# LED_Power_Ind.net
KiCad netlist of a schematic drawn in Altium Designer
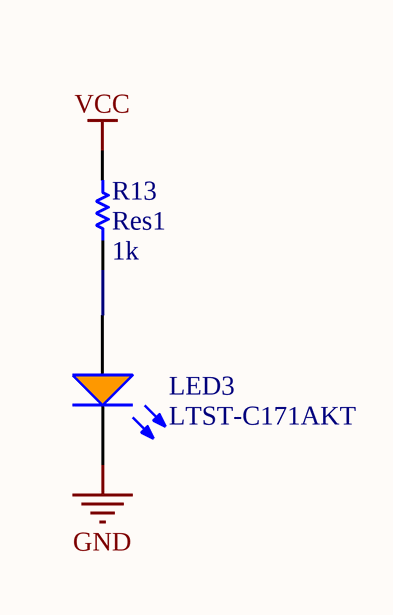
[diagram p0: LED_Power_Ind.SchDoc]

(export (version "E")
  (design (tool "Eeschema 10.0.6"))
  (components
    (comp (ref "LED3")
      (value "LTST-C171AKT")
      (footprint "LTST-C171AKT_V")
      (description "LED Uni-Color Orange, 100 mW, 120 mA, -55 to 85 degC, 2-Pin SMD, RoHS, Tape and Reel")
      (fields (field (name "MANUFACTURER") "Lite-On"))
      (libsource (lib "Altium Content Vault") (part "CMP-1674-00004-5"))
    )
    (comp (ref "R13")
      (value "Res1")
      (footprint "6-0805_L")
      (description "Resistor")
      (fields (field (name "ALTIUM_VALUE") "1k") (field (name "PUBLISHER") "Altium Limited"))
      (libsource (lib "Miscellaneous Devices") (part "Res1"))
    )
  )
  (nets
    (net (code "1") (name "GND") (class "Default")
      (node (ref "LED3") (pin "2") (pinfunction "K_2") (pintype "passive"))
    )
    (net (code "2") (name "Net-(LED3-A)") (class "Default")
      (node (ref "LED3") (pin "1") (pinfunction "A_1") (pintype "passive"))
      (node (ref "R13") (pin "1") (pinfunction "1_1") (pintype "passive"))
    )
    (net (code "3") (name "VCC") (class "Default")
      (node (ref "R13") (pin "2") (pinfunction "2_2") (pintype "passive"))
    )
  )
)
